# HLib-Comm-CAN.net
KiCad netlist of a schematic drawn in Altium Designer
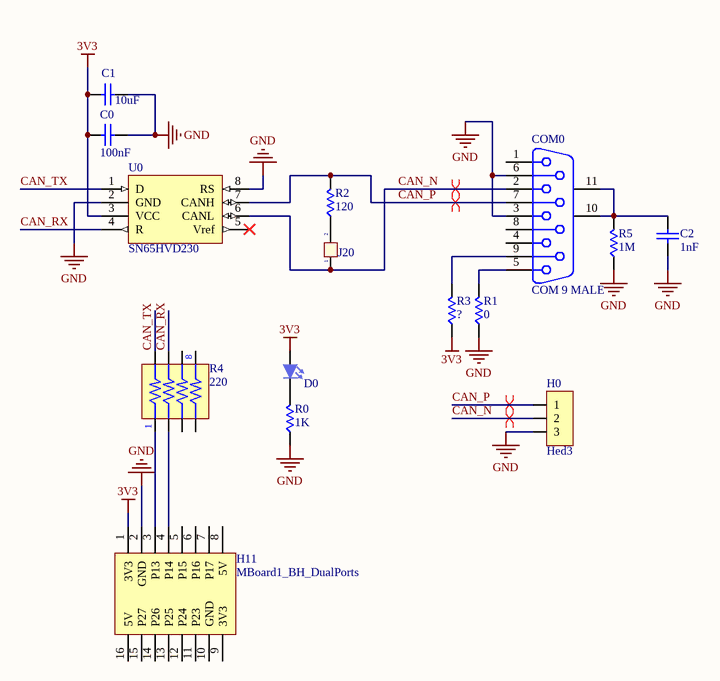
[diagram p0: HLib-Comm-CAN.SchDoc]

(export (version "E")
  (design (tool "Eeschema 10.0.6"))
  (components
    (comp (ref "C0")
      (value "100nF")
      (footprint "SM_0805_C_CERAMIC")
      (description "Non-polarity ceramic capacitor")
      (fields (field (name "Comment") "C_Ceramic") (field (name "PUBLISHER") "Altium Limited"))
      (libsource (lib "HLib_discrete_sch") (part "C_Ceramic"))
    )
    (comp (ref "C1")
      (value "10uF")
      (footprint "SM_0805_C_CERAMIC")
      (description "Non-polarity ceramic capacitor")
      (fields (field (name "Comment") "C_Ceramic") (field (name "PUBLISHER") "Altium Limited"))
      (libsource (lib "HLib_discrete_sch") (part "C_Ceramic"))
    )
    (comp (ref "C2")
      (value "1nF")
      (footprint "SM_0805_C_CERAMIC")
      (description "Non-polarity ceramic capacitor")
      (fields (field (name "Comment") "C_Ceramic") (field (name "PUBLISHER") "Altium Limited"))
      (libsource (lib "HLib_discrete_sch") (part "C_Ceramic"))
    )
    (comp (ref "COM0")
      (value "COM 9 MALE")
      (footprint "DSB 9-M")
      (description "COM 9")
      (fields (field (name "PUBLISHER") "Altium Limited"))
      (libsource (lib "VioletofSun") (part "DSB9F"))
    )
    (comp (ref "D0")
      (value "LED")
      (footprint "SM_0805_LED")
      (fields (field (name "PUBLISHER") "Altium Limited"))
      (libsource (lib "HLib_discrete_sch") (part "LED"))
    )
    (comp (ref "H0") (value "Hed3") (footprint "Hed3") (libsource (lib "Nhat_Lib") (part "Hed3")))
    (comp (ref "H11")
      (value "MBoard1_BH_DualPorts")
      (footprint "MBoard1_BH_DualPorts")
      (libsource (lib "Nhat_Lib") (part "MBoard1_BH_DualPorts"))
    )
    (comp (ref "J20")
      (value "Jumper 2")
      (footprint "HD_MALE_2_100mil_straight")
      (libsource (lib "VioletofSun") (part "JP 2"))
    )
    (comp (ref "R0")
      (value "1K")
      (footprint "SM_0805_R")
      (description "Resistor")
      (fields (field (name "Comment") "R") (field (name "PUBLISHER") "Altium Limited"))
      (libsource (lib "HLib_discrete_sch") (part "R"))
    )
    (comp (ref "R1")
      (value "0")
      (footprint "SM_0805_R")
      (description "Resistor")
      (fields (field (name "Comment") "R") (field (name "PUBLISHER") "Altium Limited"))
      (libsource (lib "HLib_discrete_sch") (part "R"))
    )
    (comp (ref "R2")
      (value "120")
      (footprint "SM_0805_R")
      (description "Resistor")
      (fields (field (name "Comment") "R") (field (name "PUBLISHER") "Altium Limited"))
      (libsource (lib "HLib_discrete_sch") (part "R"))
    )
    (comp (ref "R3")
      (value "?")
      (footprint "SM_0805_R")
      (description "Resistor")
      (fields (field (name "Comment") "R") (field (name "PUBLISHER") "Altium Limited"))
      (libsource (lib "HLib_discrete_sch") (part "R"))
    )
    (comp (ref "R4") (value "220") (footprint "RA4") (libsource (lib "Nhat_Lib") (part "RA4")))
    (comp (ref "R5")
      (value "1M")
      (footprint "SM_0805_R")
      (description "Resistor")
      (fields (field (name "Comment") "R") (field (name "PUBLISHER") "Altium Limited"))
      (libsource (lib "HLib_discrete_sch") (part "R"))
    )
    (comp (ref "U0") (value "SN65HVD230") (footprint "SO-8") (libsource (lib "Nhat_Lib") (part "SN65HVD230")))
  )
  (nets
    (net (code "1") (name "/CAN_N") (class "Default")
      (node (ref "COM0") (pin "2") (pinfunction "2_2") (pintype "passive"))
      (node (ref "H0") (pin "2") (pinfunction "2_2") (pintype "passive"))
      (node (ref "J20") (pin "1") (pinfunction "1_1") (pintype "passive"))
      (node (ref "U0") (pin "6") (pinfunction "CANL_6") (pintype "bidirectional"))
    )
    (net (code "2") (name "/CAN_P") (class "Default")
      (node (ref "COM0") (pin "7") (pinfunction "7_7") (pintype "passive"))
      (node (ref "H0") (pin "1") (pinfunction "1_1") (pintype "passive"))
      (node (ref "R2") (pin "2") (pinfunction "2_2") (pintype "passive"))
      (node (ref "U0") (pin "7") (pinfunction "CANH_7") (pintype "bidirectional"))
    )
    (net (code "3") (name "/CAN_RX") (class "Default")
      (node (ref "R4") (pin "4") (pinfunction "4_4") (pintype "passive"))
      (node (ref "U0") (pin "4") (pinfunction "R_4") (pintype "output"))
    )
    (net (code "4") (name "/CAN_TX") (class "Default")
      (node (ref "R4") (pin "2") (pinfunction "2_2") (pintype "passive"))
      (node (ref "U0") (pin "1") (pinfunction "D_1") (pintype "input"))
    )
    (net (code "5") (name "3V3") (class "Default")
      (node (ref "C0") (pin "1") (pinfunction "1_1") (pintype "passive"))
      (node (ref "C1") (pin "1") (pinfunction "1_1") (pintype "passive"))
      (node (ref "D0") (pin "1") (pinfunction "A_1") (pintype "passive"))
      (node (ref "H11") (pin "1") (pinfunction "3V3_1") (pintype "passive"))
      (node (ref "R3") (pin "1") (pinfunction "1_1") (pintype "passive"))
      (node (ref "U0") (pin "3") (pinfunction "VCC_3") (pintype "power_in"))
    )
    (net (code "6") (name "GND") (class "Default")
      (node (ref "C0") (pin "2") (pinfunction "2_2") (pintype "passive"))
      (node (ref "C1") (pin "2") (pinfunction "2_2") (pintype "passive"))
      (node (ref "C2") (pin "1") (pinfunction "1_1") (pintype "passive"))
      (node (ref "COM0") (pin "3") (pinfunction "3_3") (pintype "passive"))
      (node (ref "COM0") (pin "6") (pinfunction "6_6") (pintype "passive"))
      (node (ref "H0") (pin "3") (pinfunction "3_3") (pintype "passive"))
      (node (ref "H11") (pin "2") (pinfunction "GND_2") (pintype "passive"))
      (node (ref "R0") (pin "1") (pinfunction "1_1") (pintype "passive"))
      (node (ref "R1") (pin "1") (pinfunction "1_1") (pintype "passive"))
      (node (ref "R5") (pin "1") (pinfunction "1_1") (pintype "passive"))
      (node (ref "U0") (pin "2") (pinfunction "GND_2") (pintype "passive"))
      (node (ref "U0") (pin "8") (pinfunction "RS_8") (pintype "input"))
    )
    (net (code "7") (name "Net-(COM0-MH1)") (class "Default")
      (node (ref "C2") (pin "2") (pinfunction "2_2") (pintype "passive"))
      (node (ref "COM0") (pin "10") (pinfunction "MH1_10") (pintype "passive"))
      (node (ref "COM0") (pin "11") (pinfunction "MH2_11") (pintype "passive"))
      (node (ref "R5") (pin "2") (pinfunction "2_2") (pintype "passive"))
    )
    (net (code "8") (name "Net-(COM0-Pad5)") (class "Default")
      (node (ref "COM0") (pin "5") (pinfunction "5_5") (pintype "passive"))
      (node (ref "R1") (pin "2") (pinfunction "2_2") (pintype "passive"))
    )
    (net (code "9") (name "Net-(COM0-Pad9)") (class "Default")
      (node (ref "COM0") (pin "9") (pinfunction "9_9") (pintype "passive"))
      (node (ref "R3") (pin "2") (pinfunction "2_2") (pintype "passive"))
    )
    (net (code "10") (name "Net-(D0-K)") (class "Default")
      (node (ref "D0") (pin "2") (pinfunction "K_2") (pintype "passive"))
      (node (ref "R0") (pin "2") (pinfunction "2_2") (pintype "passive"))
    )
    (net (code "11") (name "Net-(H11-P13)") (class "Default")
      (node (ref "H11") (pin "3") (pinfunction "P13_3") (pintype "passive"))
      (node (ref "R4") (pin "1") (pinfunction "1_1") (pintype "passive"))
    )
    (net (code "12") (name "Net-(H11-P14)") (class "Default")
      (node (ref "H11") (pin "4") (pinfunction "P14_4") (pintype "passive"))
      (node (ref "R4") (pin "3") (pinfunction "3_3") (pintype "passive"))
    )
    (net (code "13") (name "Net-(J20-Pad2)") (class "Default")
      (node (ref "J20") (pin "2") (pinfunction "2_2") (pintype "passive"))
      (node (ref "R2") (pin "1") (pinfunction "1_1") (pintype "passive"))
    )
    (net (code "14") (name "unconnected-(COM0-Pad1)") (class "Default")
      (node (ref "COM0") (pin "1") (pinfunction "1_1") (pintype "passive"))
    )
    (net (code "15") (name "unconnected-(COM0-Pad4)") (class "Default")
      (node (ref "COM0") (pin "4") (pinfunction "4_4") (pintype "passive"))
    )
    (net (code "16") (name "unconnected-(COM0-Pad8)") (class "Default")
      (node (ref "COM0") (pin "8") (pinfunction "8_8") (pintype "passive"))
    )
    (net (code "17") (name "unconnected-(H11-3V3-Pad9)") (class "Default")
      (node (ref "H11") (pin "9") (pinfunction "3V3_9") (pintype "passive"))
    )
    (net (code "18") (name "unconnected-(H11-5V-Pad8)") (class "Default")
      (node (ref "H11") (pin "8") (pinfunction "5V_8") (pintype "passive"))
    )
    (net (code "19") (name "unconnected-(H11-5V-Pad16)") (class "Default")
      (node (ref "H11") (pin "16") (pinfunction "5V_16") (pintype "passive"))
    )
    (net (code "20") (name "unconnected-(H11-GND-Pad10)") (class "Default")
      (node (ref "H11") (pin "10") (pinfunction "GND_10") (pintype "passive"))
    )
    (net (code "21") (name "unconnected-(H11-P15-Pad5)") (class "Default")
      (node (ref "H11") (pin "5") (pinfunction "P15_5") (pintype "passive"))
    )
    (net (code "22") (name "unconnected-(H11-P16-Pad6)") (class "Default")
      (node (ref "H11") (pin "6") (pinfunction "P16_6") (pintype "passive"))
    )
    (net (code "23") (name "unconnected-(H11-P17-Pad7)") (class "Default")
      (node (ref "H11") (pin "7") (pinfunction "P17_7") (pintype "passive"))
    )
    (net (code "24") (name "unconnected-(H11-P23-Pad11)") (class "Default")
      (node (ref "H11") (pin "11") (pinfunction "P23_11") (pintype "passive"))
    )
    (net (code "25") (name "unconnected-(H11-P24-Pad12)") (class "Default")
      (node (ref "H11") (pin "12") (pinfunction "P24_12") (pintype "passive"))
    )
    (net (code "26") (name "unconnected-(H11-P25-Pad13)") (class "Default")
      (node (ref "H11") (pin "13") (pinfunction "P25_13") (pintype "passive"))
    )
    (net (code "27") (name "unconnected-(H11-P26-Pad14)") (class "Default")
      (node (ref "H11") (pin "14") (pinfunction "P26_14") (pintype "passive"))
    )
    (net (code "28") (name "unconnected-(H11-P27-Pad15)") (class "Default")
      (node (ref "H11") (pin "15") (pinfunction "P27_15") (pintype "passive"))
    )
    (net (code "29") (name "unconnected-(R4-Pad5)") (class "Default")
      (node (ref "R4") (pin "5") (pinfunction "5_5") (pintype "passive"))
    )
    (net (code "30") (name "unconnected-(R4-Pad6)") (class "Default")
      (node (ref "R4") (pin "6") (pinfunction "6_6") (pintype "passive"))
    )
    (net (code "31") (name "unconnected-(R4-Pad7)") (class "Default")
      (node (ref "R4") (pin "7") (pinfunction "7_7") (pintype "passive"))
    )
    (net (code "32") (name "unconnected-(R4-Pad8)") (class "Default")
      (node (ref "R4") (pin "8") (pinfunction "8_8") (pintype "passive"))
    )
    (net (code "33") (name "unconnected-(U0-Vref-Pad5)") (class "Default")
      (node (ref "U0") (pin "5") (pinfunction "Vref_5") (pintype "output+no_connect"))
    )
  )
)
